# FuenteAlimentacion.net
KiCad netlist of a schematic drawn in Altium Designer
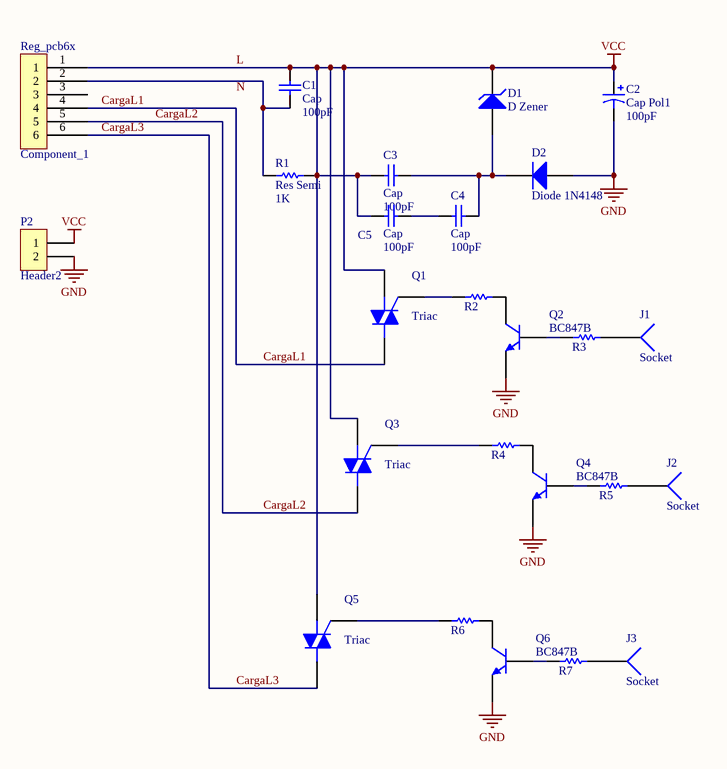
[diagram p0: FuenteAlimentacion.SchDoc]

(export (version "E")
  (design (tool "Eeschema 10.0.6"))
  (components
    (comp (ref "C1")
      (value "Cap")
      (footprint "CAP400V")
      (description "Capacitor")
      (fields (field (name "ALTIUM_VALUE") "100pF") (field (name "PUBLISHER") "Altium Limited"))
      (libsource (lib "Miscellaneous Devices") (part "Cap"))
    )
    (comp (ref "C2")
      (value "Cap Pol1")
      (footprint "CAPPR7.5-16x35")
      (description "Polarized Capacitor (Radial)")
      (fields (field (name "ALTIUM_VALUE") "100pF") (field (name "PUBLISHER") "Altium Limited"))
      (libsource (lib "Miscellaneous Devices") (part "Cap Pol1"))
    )
    (comp (ref "C3")
      (value "Cap")
      (footprint "CAP400V")
      (description "Capacitor")
      (fields (field (name "ALTIUM_VALUE") "100pF") (field (name "PUBLISHER") "Altium Limited"))
      (libsource (lib "Miscellaneous Devices") (part "Cap"))
    )
    (comp (ref "C4")
      (value "Cap")
      (footprint "CAP250V")
      (description "Capacitor")
      (fields (field (name "ALTIUM_VALUE") "100pF") (field (name "PUBLISHER") "Altium Limited"))
      (libsource (lib "Miscellaneous Devices") (part "Cap"))
    )
    (comp (ref "C5")
      (value "Cap")
      (footprint "CAP250V")
      (description "Capacitor")
      (fields (field (name "ALTIUM_VALUE") "100pF") (field (name "PUBLISHER") "Altium Limited"))
      (libsource (lib "Miscellaneous Devices") (part "Cap"))
    )
    (comp (ref "D1")
      (value "D Zener")
      (footprint "Zener")
      (description "Zener Diode")
      (fields (field (name "PUBLISHER") "Altium Limited"))
      (libsource (lib "Miscellaneous Devices") (part "D Zener"))
    )
    (comp (ref "D2")
      (value "Diode 1N4148")
      (footprint "1N4148SMD")
      (description "High Conductance Fast Diode")
      (fields (field (name "PUBLISHER") "Altium Limited"))
      (libsource (lib "Miscellaneous Devices") (part "Diode 1N4148"))
    )
    (comp (ref "J1")
      (value "Socket")
      (footprint "PIN1")
      (fields (field (name "PUBLISHER") "Altium Limited"))
      (libsource (lib "Miscellaneous Connectors") (part "Socket"))
    )
    (comp (ref "J2")
      (value "Socket")
      (footprint "PIN1")
      (fields (field (name "PUBLISHER") "Altium Limited"))
      (libsource (lib "Miscellaneous Connectors") (part "Socket"))
    )
    (comp (ref "J3")
      (value "Socket")
      (footprint "PIN1")
      (fields (field (name "PUBLISHER") "Altium Limited"))
      (libsource (lib "Miscellaneous Connectors") (part "Socket"))
    )
    (comp (ref "P2") (value "Header2") (footprint "Header2Macho") (libsource (lib "epf") (part "Header2")))
    (comp (ref "Q1")
      (value "Triac")
      (footprint "369-03")
      (description "Silicon Bidirectional Triode Thyristor")
      (fields (field (name "PUBLISHER") "Altium Limited"))
      (libsource (lib "Miscellaneous Devices") (part "Triac"))
    )
    (comp (ref "Q2")
      (value "BC847B")
      (footprint "SOT23")
      (description "NPN General-purpose Transistor")
      (fields (field (name "PUBLISHER") "Altium Limited"))
      (libsource (lib "Philips Discrete BJT - Low Power") (part "BC847B"))
    )
    (comp (ref "Q3")
      (value "Triac")
      (footprint "369-03")
      (description "Silicon Bidirectional Triode Thyristor")
      (fields (field (name "PUBLISHER") "Altium Limited"))
      (libsource (lib "Miscellaneous Devices") (part "Triac"))
    )
    (comp (ref "Q4")
      (value "BC847B")
      (footprint "SOT23")
      (description "NPN General-purpose Transistor")
      (fields (field (name "PUBLISHER") "Altium Limited"))
      (libsource (lib "Philips Discrete BJT - Low Power") (part "BC847B"))
    )
    (comp (ref "Q5")
      (value "Triac")
      (footprint "369-03")
      (description "Silicon Bidirectional Triode Thyristor")
      (fields (field (name "PUBLISHER") "Altium Limited"))
      (libsource (lib "Miscellaneous Devices") (part "Triac"))
    )
    (comp (ref "Q6")
      (value "BC847B")
      (footprint "SOT23")
      (description "NPN General-purpose Transistor")
      (fields (field (name "PUBLISHER") "Altium Limited"))
      (libsource (lib "Philips Discrete BJT - Low Power") (part "BC847B"))
    )
    (comp (ref "R1")
      (value "Res Semi")
      (footprint "AXIAL-0.5")
      (description "Semiconductor Resistor")
      (fields (field (name "ALTIUM_VALUE") "1K") (field (name "PUBLISHER") "Altium Limited"))
      (libsource (lib "Miscellaneous Devices") (part "Res Semi"))
    )
    (comp (ref "R2") (value "Resistor") (footprint "0805_RES") (libsource (lib "epf") (part "Res")))
    (comp (ref "R3") (value "Resistor") (footprint "0805_RES") (libsource (lib "epf") (part "Res")))
    (comp (ref "R4") (value "Resistor") (footprint "0805_RES") (libsource (lib "epf") (part "Res")))
    (comp (ref "R5") (value "Resistor") (footprint "0805_RES") (libsource (lib "epf") (part "Res")))
    (comp (ref "R6") (value "Resistor") (footprint "0805_RES") (libsource (lib "epf") (part "Res")))
    (comp (ref "R7") (value "Resistor") (footprint "0805_RES") (libsource (lib "epf") (part "Res")))
    (comp (ref "Reg_pcb6x")
      (value "Component_1")
      (footprint "PCBComponent_1")
      (libsource (lib "Reg_pcbx6") (part "Component_1"))
    )
  )
  (nets
    (net (code "1") (name "/CargaL1") (class "Default")
      (node (ref "Q1") (pin "2") (pinfunction "M2_2") (pintype "passive"))
      (node (ref "Reg_pcb6x") (pin "4") (pinfunction "4_4") (pintype "passive"))
    )
    (net (code "2") (name "/CargaL2") (class "Default")
      (node (ref "Q3") (pin "2") (pinfunction "M2_2") (pintype "passive"))
      (node (ref "Reg_pcb6x") (pin "5") (pinfunction "5_5") (pintype "passive"))
    )
    (net (code "3") (name "/CargaL3") (class "Default")
      (node (ref "Q5") (pin "2") (pinfunction "M2_2") (pintype "passive"))
      (node (ref "Reg_pcb6x") (pin "6") (pinfunction "6_6") (pintype "passive"))
    )
    (net (code "5") (name "GND") (class "Default")
      (node (ref "C2") (pin "2") (pinfunction "2_2") (pintype "passive"))
      (node (ref "D2") (pin "1") (pinfunction "A_1") (pintype "passive"))
      (node (ref "P2") (pin "2") (pinfunction "2_2") (pintype "passive"))
      (node (ref "Q2") (pin "2") (pinfunction "E_2") (pintype "passive"))
      (node (ref "Q4") (pin "2") (pinfunction "E_2") (pintype "passive"))
      (node (ref "Q6") (pin "2") (pinfunction "E_2") (pintype "passive"))
    )
    (net (code "6") (name "Net-(C1-Pad1)") (class "Default")
      (node (ref "C1") (pin "1") (pinfunction "1_1") (pintype "passive"))
      (node (ref "R1") (pin "1") (pinfunction "1_1") (pintype "passive"))
      (node (ref "Reg_pcb6x") (pin "2") (pinfunction "2_2") (pintype "passive"))
    )
    (net (code "7") (name "Net-(C4-Pad1)") (class "Default")
      (node (ref "C4") (pin "1") (pinfunction "1_1") (pintype "passive"))
      (node (ref "C5") (pin "2") (pinfunction "2_2") (pintype "passive"))
    )
    (net (code "8") (name "Net-(D1-A)") (class "Default")
      (node (ref "C3") (pin "2") (pinfunction "2_2") (pintype "passive"))
      (node (ref "C4") (pin "2") (pinfunction "2_2") (pintype "passive"))
      (node (ref "D1") (pin "1") (pinfunction "A_1") (pintype "passive"))
      (node (ref "D2") (pin "2") (pinfunction "K_2") (pintype "passive"))
    )
    (net (code "9") (name "Net-(J1-Pad1)") (class "Default")
      (node (ref "J1") (pin "1") (pinfunction "1_1") (pintype "passive"))
      (node (ref "R3") (pin "2") (pinfunction "2_2") (pintype "passive"))
    )
    (net (code "10") (name "Net-(J2-Pad1)") (class "Default")
      (node (ref "J2") (pin "1") (pinfunction "1_1") (pintype "passive"))
      (node (ref "R5") (pin "2") (pinfunction "2_2") (pintype "passive"))
    )
    (net (code "11") (name "Net-(J3-Pad1)") (class "Default")
      (node (ref "J3") (pin "1") (pinfunction "1_1") (pintype "passive"))
      (node (ref "R7") (pin "2") (pinfunction "2_2") (pintype "passive"))
    )
    (net (code "12") (name "Net-(Q1-G)") (class "Default")
      (node (ref "Q1") (pin "3") (pinfunction "G_3") (pintype "passive"))
      (node (ref "R2") (pin "1") (pinfunction "1_1") (pintype "passive"))
    )
    (net (code "13") (name "Net-(Q2-B)") (class "Default")
      (node (ref "Q2") (pin "1") (pinfunction "B_1") (pintype "passive"))
      (node (ref "R3") (pin "1") (pinfunction "1_1") (pintype "passive"))
    )
    (net (code "14") (name "Net-(Q2-C)") (class "Default")
      (node (ref "Q2") (pin "3") (pinfunction "C_3") (pintype "passive"))
      (node (ref "R2") (pin "2") (pinfunction "2_2") (pintype "passive"))
    )
    (net (code "15") (name "Net-(Q3-G)") (class "Default")
      (node (ref "Q3") (pin "3") (pinfunction "G_3") (pintype "passive"))
      (node (ref "R4") (pin "1") (pinfunction "1_1") (pintype "passive"))
    )
    (net (code "16") (name "Net-(Q4-B)") (class "Default")
      (node (ref "Q4") (pin "1") (pinfunction "B_1") (pintype "passive"))
      (node (ref "R5") (pin "1") (pinfunction "1_1") (pintype "passive"))
    )
    (net (code "17") (name "Net-(Q4-C)") (class "Default")
      (node (ref "Q4") (pin "3") (pinfunction "C_3") (pintype "passive"))
      (node (ref "R4") (pin "2") (pinfunction "2_2") (pintype "passive"))
    )
    (net (code "18") (name "Net-(Q5-G)") (class "Default")
      (node (ref "Q5") (pin "3") (pinfunction "G_3") (pintype "passive"))
      (node (ref "R6") (pin "1") (pinfunction "1_1") (pintype "passive"))
    )
    (net (code "19") (name "Net-(Q6-B)") (class "Default")
      (node (ref "Q6") (pin "1") (pinfunction "B_1") (pintype "passive"))
      (node (ref "R7") (pin "1") (pinfunction "1_1") (pintype "passive"))
    )
    (net (code "20") (name "Net-(Q6-C)") (class "Default")
      (node (ref "Q6") (pin "3") (pinfunction "C_3") (pintype "passive"))
      (node (ref "R6") (pin "2") (pinfunction "2_2") (pintype "passive"))
    )
    (net (code "21") (name "VCC") (class "Default")
      (node (ref "C1") (pin "2") (pinfunction "2_2") (pintype "passive"))
      (node (ref "C2") (pin "1") (pinfunction "1_1") (pintype "passive"))
      (node (ref "C3") (pin "1") (pinfunction "1_1") (pintype "passive"))
      (node (ref "C5") (pin "1") (pinfunction "1_1") (pintype "passive"))
      (node (ref "D1") (pin "2") (pinfunction "K_2") (pintype "passive"))
      (node (ref "P2") (pin "1") (pinfunction "1_1") (pintype "passive"))
      (node (ref "Q1") (pin "1") (pinfunction "M1_1") (pintype "passive"))
      (node (ref "Q3") (pin "1") (pinfunction "M1_1") (pintype "passive"))
      (node (ref "Q5") (pin "1") (pinfunction "M1_1") (pintype "passive"))
      (node (ref "R1") (pin "2") (pinfunction "2_2") (pintype "passive"))
      (node (ref "Reg_pcb6x") (pin "1") (pinfunction "1_1") (pintype "passive"))
    )
    (net (code "22") (name "unconnected-(Reg_pcb6x-Pad3)") (class "Default")
      (node (ref "Reg_pcb6x") (pin "3") (pinfunction "3_3") (pintype "passive"))
    )
  )
)
